# TM.net
KiCad netlist of a schematic drawn in EAGLE
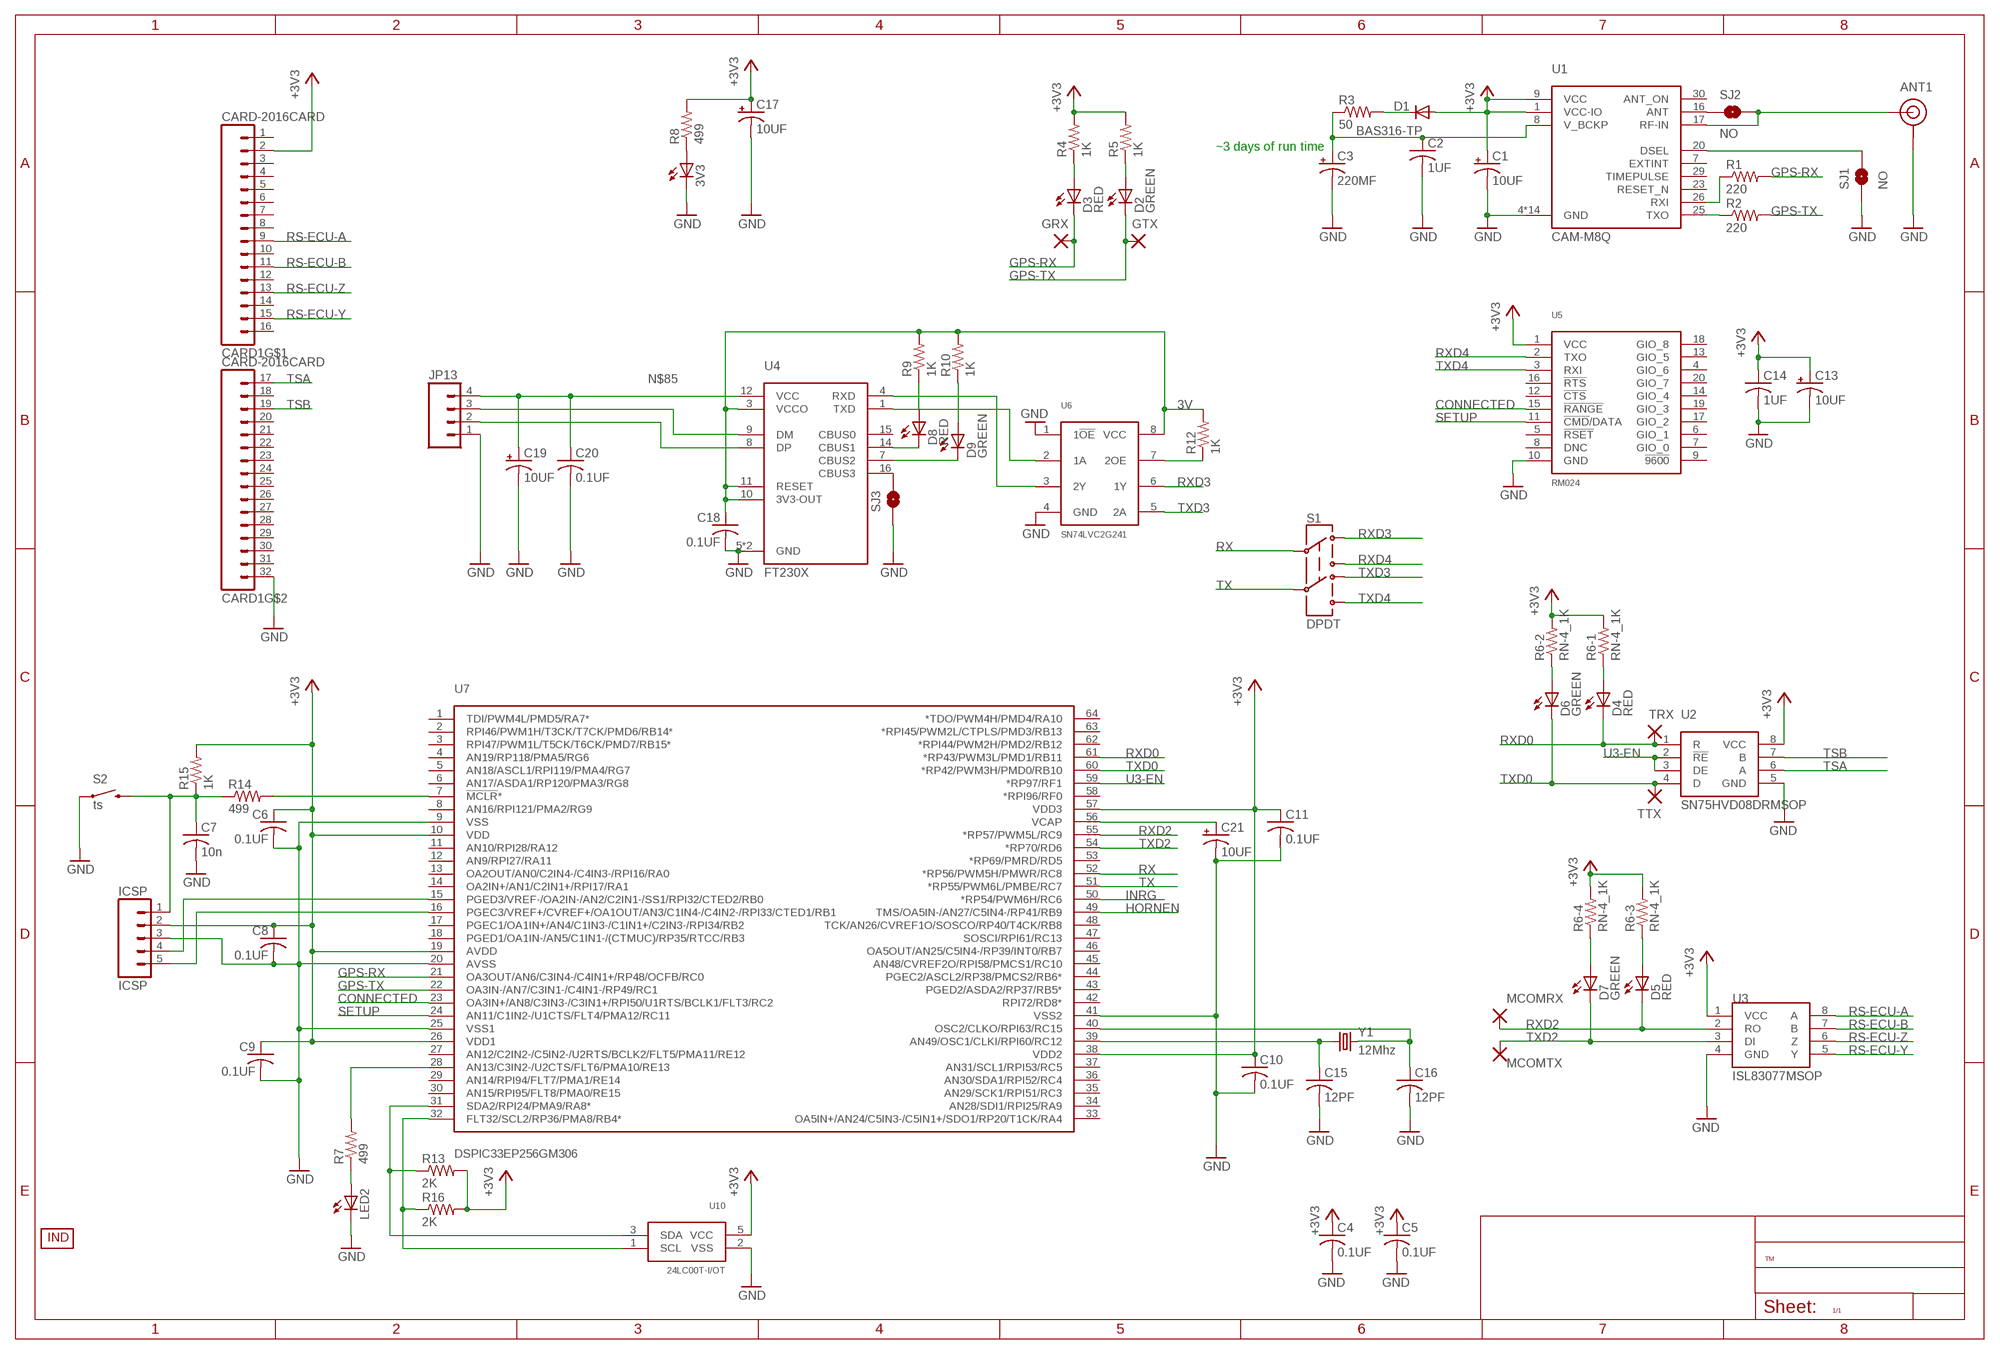
[diagram p0: schematic, sheet 1]

(export (version "E")
  (design (tool "Eeschema 10.0.6"))
  (components
    (comp (ref "3V3")
      (value "LEDCHIP-LED0805")
      (footprint "eagle-import:CHIP-LED0805")
      (libsource (lib "eagle-import") (part "LEDCHIP-LED0805"))
    )
    (comp (ref "ANT1")
      (value "CONMCX002")
      (footprint "eagle-import:CONSMA002")
      (libsource (lib "eagle-import") (part "SMA"))
    )
    (comp (ref "C1")
      (value "10UF")
      (footprint "eagle-import:EIA3216-16V")
      (fields (field (name "PARTNO") "T491A106M016AT"))
      (libsource (lib "eagle-import") (part "CAP-POL_10UF_16V"))
    )
    (comp (ref "C2")
      (value "1UF")
      (footprint "eagle-import:0805")
      (fields (field (name "PARTNO") "UMK212F105ZG-T"))
      (libsource (lib "eagle-import") (part "CAP_1UF_50V_0805"))
    )
    (comp (ref "C3")
      (value "220MF")
      (footprint "eagle-import:EEC-S0HD224V")
      (fields (field (name "PARTNO") "EEC-S0HD224V"))
      (libsource (lib "eagle-import") (part "CAP-POL_220MF_5.5V"))
    )
    (comp (ref "C4")
      (value "0.1UF")
      (footprint "eagle-import:0805")
      (fields (field (name "PARTNO") "CC0805ZRY5V9BB104"))
      (libsource (lib "eagle-import") (part "CAP_0.1UF_50V_0805"))
    )
    (comp (ref "C5")
      (value "0.1UF")
      (footprint "eagle-import:0805")
      (fields (field (name "PARTNO") "CC0805ZRY5V9BB104"))
      (libsource (lib "eagle-import") (part "CAP_0.1UF_50V_0805"))
    )
    (comp (ref "C6")
      (value "0.1UF")
      (footprint "eagle-import:0805")
      (fields (field (name "PARTNO") "CC0805ZRY5V9BB104"))
      (libsource (lib "eagle-import") (part "CAP_0.1UF_50V_0805"))
    )
    (comp (ref "C7")
      (value "10n")
      (footprint "eagle-import:C0805")
      (libsource (lib "eagle-import") (part "C-USC0805"))
    )
    (comp (ref "C8")
      (value "0.1UF")
      (footprint "eagle-import:0805")
      (fields (field (name "PARTNO") "CC0805ZRY5V9BB104"))
      (libsource (lib "eagle-import") (part "CAP_0.1UF_50V_0805"))
    )
    (comp (ref "C9")
      (value "0.1UF")
      (footprint "eagle-import:0805")
      (fields (field (name "PARTNO") "CC0805ZRY5V9BB104"))
      (libsource (lib "eagle-import") (part "CAP_0.1UF_50V_0805"))
    )
    (comp (ref "C10")
      (value "0.1UF")
      (footprint "eagle-import:0805")
      (fields (field (name "PARTNO") "CC0805ZRY5V9BB104"))
      (libsource (lib "eagle-import") (part "CAP_0.1UF_50V_0805"))
    )
    (comp (ref "C11")
      (value "0.1UF")
      (footprint "eagle-import:0805")
      (fields (field (name "PARTNO") "CC0805ZRY5V9BB104"))
      (libsource (lib "eagle-import") (part "CAP_0.1UF_50V_0805"))
    )
    (comp (ref "C13")
      (value "10UF")
      (footprint "eagle-import:EIA3216-16V")
      (fields (field (name "PARTNO") "T491A106M016AT"))
      (libsource (lib "eagle-import") (part "CAP-POL_10UF_16V"))
    )
    (comp (ref "C14")
      (value "1UF")
      (footprint "eagle-import:0805")
      (fields (field (name "PARTNO") "UMK212F105ZG-T"))
      (libsource (lib "eagle-import") (part "CAP_1UF_50V_0805"))
    )
    (comp (ref "C15")
      (value "12PF")
      (footprint "eagle-import:0805")
      (fields (field (name "PARTNO") "CL21C120JBANNNC"))
      (libsource (lib "eagle-import") (part "CAP_12PF_50V_0805"))
    )
    (comp (ref "C16")
      (value "12PF")
      (footprint "eagle-import:0805")
      (fields (field (name "PARTNO") "CL21C120JBANNNC"))
      (libsource (lib "eagle-import") (part "CAP_12PF_50V_0805"))
    )
    (comp (ref "C17")
      (value "10UF")
      (footprint "eagle-import:EIA3216-16V")
      (fields (field (name "PARTNO") "T491A106M016AT"))
      (libsource (lib "eagle-import") (part "CAP-POL_10UF_16V"))
    )
    (comp (ref "C18")
      (value "0.1UF")
      (footprint "eagle-import:0805")
      (fields (field (name "PARTNO") "CC0805ZRY5V9BB104"))
      (libsource (lib "eagle-import") (part "CAP_0.1UF_50V_0805"))
    )
    (comp (ref "C19")
      (value "10UF")
      (footprint "eagle-import:EIA3216-16V")
      (fields (field (name "PARTNO") "T491A106M016AT"))
      (libsource (lib "eagle-import") (part "CAP-POL_10UF_16V"))
    )
    (comp (ref "C20")
      (value "0.1UF")
      (footprint "eagle-import:0805")
      (fields (field (name "PARTNO") "CC0805ZRY5V9BB104"))
      (libsource (lib "eagle-import") (part "CAP_0.1UF_50V_0805"))
    )
    (comp (ref "C21")
      (value "10UF")
      (footprint "eagle-import:EIA3216-16V")
      (fields (field (name "PARTNO") "T491A106M016AT"))
      (libsource (lib "eagle-import") (part "CAP-POL_10UF_16V"))
    )
    (comp (ref "CARD1")
      (value "CARD-2016CARD")
      (footprint "eagle-import:CARD-2016")
      (libsource (lib "eagle-import") (part "CARD-2016CARD"))
    )
    (comp (ref "D1")
      (value "BAS316-TP")
      (footprint "eagle-import:SOD-323")
      (libsource (lib "eagle-import") (part "DIODESOD"))
    )
    (comp (ref "D2")
      (value "GREEN")
      (footprint "eagle-import:CHIP_LED0805")
      (fields (field (name "PARTNO") "LTST-S220GKT"))
      (libsource (lib "eagle-import") (part "LED_GREEN"))
    )
    (comp (ref "D3")
      (value "RED")
      (footprint "eagle-import:CHIP_LED0805")
      (fields (field (name "PARTNO") "LH R974-LP-1"))
      (libsource (lib "eagle-import") (part "LED_RED"))
    )
    (comp (ref "D4")
      (value "RED")
      (footprint "eagle-import:CHIP_LED0805")
      (fields (field (name "PARTNO") "LH R974-LP-1"))
      (libsource (lib "eagle-import") (part "LED_RED"))
    )
    (comp (ref "D5")
      (value "RED")
      (footprint "eagle-import:CHIP_LED0805")
      (fields (field (name "PARTNO") "LH R974-LP-1"))
      (libsource (lib "eagle-import") (part "LED_RED"))
    )
    (comp (ref "D6")
      (value "GREEN")
      (footprint "eagle-import:CHIP_LED0805")
      (fields (field (name "PARTNO") "LTST-S220GKT"))
      (libsource (lib "eagle-import") (part "LED_GREEN"))
    )
    (comp (ref "D7")
      (value "GREEN")
      (footprint "eagle-import:CHIP_LED0805")
      (fields (field (name "PARTNO") "LTST-S220GKT"))
      (libsource (lib "eagle-import") (part "LED_GREEN"))
    )
    (comp (ref "D8")
      (value "RED")
      (footprint "eagle-import:CHIP_LED0805")
      (fields (field (name "PARTNO") "LH R974-LP-1"))
      (libsource (lib "eagle-import") (part "LED_RED"))
    )
    (comp (ref "D9")
      (value "GREEN")
      (footprint "eagle-import:CHIP_LED0805")
      (fields (field (name "PARTNO") "LTST-S220GKT"))
      (libsource (lib "eagle-import") (part "LED_GREEN"))
    )
    (comp (ref "GRX")
      (value "TP")
      (footprint "eagle-import:0603")
      (fields (field (name "PARTNO") "1625854-3"))
      (libsource (lib "eagle-import") (part "TP"))
    )
    (comp (ref "GTX")
      (value "TP")
      (footprint "eagle-import:0603")
      (fields (field (name "PARTNO") "1625854-3"))
      (libsource (lib "eagle-import") (part "TP"))
    )
    (comp (ref "ICSP")
      (value "ICSP")
      (footprint "eagle-import:1X05_LOCK_LONGPADS")
      (libsource (lib "eagle-import") (part "M05LOCK_LONGPADS"))
    )
    (comp (ref "JP13")
      (value "M04POLAR_LOCK")
      (footprint "eagle-import:MOLEX-1X4_LOCK")
      (libsource (lib "eagle-import") (part "M04POLAR_LOCK"))
    )
    (comp (ref "LED2")
      (value "LEDCHIP-LED0805")
      (footprint "eagle-import:CHIP-LED0805")
      (libsource (lib "eagle-import") (part "LEDCHIP-LED0805"))
    )
    (comp (ref "MCOMRX")
      (value "TP")
      (footprint "eagle-import:0603")
      (fields (field (name "PARTNO") "1625854-3"))
      (libsource (lib "eagle-import") (part "TP"))
    )
    (comp (ref "MCOMTX")
      (value "TP")
      (footprint "eagle-import:0603")
      (fields (field (name "PARTNO") "1625854-3"))
      (libsource (lib "eagle-import") (part "TP"))
    )
    (comp (ref "R1")
      (value "220")
      (footprint "eagle-import:0805")
      (fields (field (name "PARTNO") "RC0805FR-07220RL"))
      (libsource (lib "eagle-import") (part "RES_220_1%_0805"))
    )
    (comp (ref "R2")
      (value "220")
      (footprint "eagle-import:0805")
      (fields (field (name "PARTNO") "RC0805FR-07220RL"))
      (libsource (lib "eagle-import") (part "RES_220_1%_0805"))
    )
    (comp (ref "R3")
      (value "50")
      (footprint "eagle-import:R2010")
      (libsource (lib "eagle-import") (part "RESISTOR2010"))
    )
    (comp (ref "R4")
      (value "1K")
      (footprint "eagle-import:0805")
      (fields (field (name "PARTNO") "RC0805FR-071KL"))
      (libsource (lib "eagle-import") (part "RES_1K_1%_0805"))
    )
    (comp (ref "R5")
      (value "1K")
      (footprint "eagle-import:0805")
      (fields (field (name "PARTNO") "RC0805FR-071KL"))
      (libsource (lib "eagle-import") (part "RES_1K_1%_0805"))
    )
    (comp (ref "R6")
      (value "RN-4_1K")
      (footprint "eagle-import:MNR14")
      (fields (field (name "PARTNO") "MNR14ERAPJ102"))
      (libsource (lib "eagle-import") (part "RN-4_1K"))
    )
    (comp (ref "R7")
      (value "499")
      (footprint "eagle-import:0805")
      (fields (field (name "PARTNO") "RC0805FR-07499RL"))
      (libsource (lib "eagle-import") (part "RES_499_1%_0805"))
    )
    (comp (ref "R8")
      (value "499")
      (footprint "eagle-import:0805")
      (fields (field (name "PARTNO") "RC0805FR-07499RL"))
      (libsource (lib "eagle-import") (part "RES_499_1%_0805"))
    )
    (comp (ref "R9")
      (value "1K")
      (footprint "eagle-import:0805")
      (fields (field (name "PARTNO") "RC0805FR-071KL"))
      (libsource (lib "eagle-import") (part "RES_1K_1%_0805"))
    )
    (comp (ref "R10")
      (value "1K")
      (footprint "eagle-import:0805")
      (fields (field (name "PARTNO") "RC0805FR-071KL"))
      (libsource (lib "eagle-import") (part "RES_1K_1%_0805"))
    )
    (comp (ref "R12")
      (value "1K")
      (footprint "eagle-import:0805")
      (fields (field (name "PARTNO") "RC0805FR-071KL"))
      (libsource (lib "eagle-import") (part "RES_1K_1%_0805"))
    )
    (comp (ref "R13")
      (value "2K")
      (footprint "eagle-import:0805")
      (fields (field (name "PARTNO") "RC0805FR-072KL"))
      (libsource (lib "eagle-import") (part "RES_2K_1%_0805"))
    )
    (comp (ref "R14")
      (value "499")
      (footprint "eagle-import:0805")
      (fields (field (name "PARTNO") "RC0805FR-07499RL"))
      (libsource (lib "eagle-import") (part "RES_499_1%_0805"))
    )
    (comp (ref "R15")
      (value "1K")
      (footprint "eagle-import:0805")
      (fields (field (name "PARTNO") "RC0805FR-071KL"))
      (libsource (lib "eagle-import") (part "RES_1K_1%_0805"))
    )
    (comp (ref "R16")
      (value "2K")
      (footprint "eagle-import:0805")
      (fields (field (name "PARTNO") "RC0805FR-072KL"))
      (libsource (lib "eagle-import") (part "RES_2K_1%_0805"))
    )
    (comp (ref "S1")
      (value "DPDT")
      (footprint "eagle-import:AYZ0202")
      (libsource (lib "eagle-import") (part "SWITCH-DPDTAYZ0202"))
    )
    (comp (ref "S2")
      (value "ts")
      (footprint "eagle-import:TACTILE_SWITCH_SMD-2")
      (libsource (lib "eagle-import") (part "SWITCH-MOMENTARY-2SMD-2"))
    )
    (comp (ref "SJ1")
      (value "NO")
      (footprint "eagle-import:SJ_2S-NO")
      (libsource (lib "eagle-import") (part "SOLDERJUMPERNO"))
    )
    (comp (ref "SJ2")
      (value "NO")
      (footprint "eagle-import:SJ_2S-NO")
      (libsource (lib "eagle-import") (part "SOLDERJUMPERNO"))
    )
    (comp (ref "SJ3")
      (value "JUMPER-PAD-2-NOYES_SILK")
      (footprint "eagle-import:PAD-JUMPER-2-NO_YES_SILK")
      (libsource (lib "eagle-import") (part "JUMPER-PAD-2-NOYES_SILK"))
    )
    (comp (ref "TRX")
      (value "TP")
      (footprint "eagle-import:0603")
      (fields (field (name "PARTNO") "1625854-3"))
      (libsource (lib "eagle-import") (part "TP"))
    )
    (comp (ref "TTX")
      (value "TP")
      (footprint "eagle-import:0603")
      (fields (field (name "PARTNO") "1625854-3"))
      (libsource (lib "eagle-import") (part "TP"))
    )
    (comp (ref "U$3")
      (value "INDPK1")
      (footprint "eagle-import:PICKIT-PIN-1")
      (libsource (lib "eagle-import") (part "INDPK1"))
    )
    (comp (ref "U1")
      (value "CAM-M8Q")
      (footprint "eagle-import:CAM-M8Q")
      (libsource (lib "eagle-import") (part "CAM-M8Q"))
    )
    (comp (ref "U2")
      (value "SN75HVD08DRMSOP")
      (footprint "eagle-import:MSOP-8")
      (fields (field (name "PARTNO") "ISL83072EIUZA-T"))
      (libsource (lib "eagle-import") (part "SN75HVD08DRMSOP"))
    )
    (comp (ref "U3")
      (value "ISL83077MSOP")
      (footprint "eagle-import:MSOP8")
      (fields (field (name "PARTNO") "ISL83072EIUZA-T"))
      (libsource (lib "eagle-import") (part "ISL83077MSOP"))
    )
    (comp (ref "U4")
      (value "FT230X")
      (footprint "eagle-import:SSOP-16")
      (fields (field (name "PARTNO") "FT230XS-R"))
      (libsource (lib "eagle-import") (part "FT230X"))
    )
    (comp (ref "U5")
      (value "RM024")
      (footprint "eagle-import:RM024-TH")
      (libsource (lib "eagle-import") (part "RM024"))
    )
    (comp (ref "U6")
      (value "SN74LVC2G241")
      (footprint "eagle-import:VFSOP-8")
      (fields (field (name "PARTNO") "SN74LVC2G241DCUR"))
      (libsource (lib "eagle-import") (part "SN74LVC2G241"))
    )
    (comp (ref "U7")
      (value "DSPIC33EP256GM306")
      (footprint "eagle-import:TQFP-64")
      (libsource (lib "eagle-import") (part "DSPIC33EP256GM306"))
    )
    (comp (ref "U10")
      (value "24LC00T-I/OT")
      (footprint "eagle-import:SOT23-5")
      (libsource (lib "eagle-import") (part "24LC00T-I/OT"))
    )
    (comp (ref "Y1")
      (value "12Mhz")
      (footprint "eagle-import:CRYSTAL-SMD-5X3")
      (libsource (lib "eagle-import") (part "CRYSTAL5X3"))
    )
  )
  (nets
    (net (code "1") (name "+3V3") (class "Default")
      (node (ref "C1") (pin "A") (pinfunction "+_A") (pintype "passive"))
      (node (ref "C10") (pin "1") (pinfunction "+_1") (pintype "passive"))
      (node (ref "C11") (pin "1") (pinfunction "+_1") (pintype "passive"))
      (node (ref "C13") (pin "A") (pinfunction "+_A") (pintype "passive"))
      (node (ref "C14") (pin "1") (pinfunction "+_1") (pintype "passive"))
      (node (ref "C17") (pin "A") (pinfunction "+_A") (pintype "passive"))
      (node (ref "C4") (pin "1") (pinfunction "+_1") (pintype "passive"))
      (node (ref "C5") (pin "1") (pinfunction "+_1") (pintype "passive"))
      (node (ref "C6") (pin "1") (pinfunction "+_1") (pintype "passive"))
      (node (ref "C8") (pin "1") (pinfunction "+_1") (pintype "passive"))
      (node (ref "C9") (pin "1") (pinfunction "+_1") (pintype "passive"))
      (node (ref "CARD1") (pin "2") (pinfunction "2_2") (pintype "passive"))
      (node (ref "D1") (pin "2") (pinfunction "A_2") (pintype "passive"))
      (node (ref "ICSP") (pin "2") (pinfunction "2_2") (pintype "passive"))
      (node (ref "R13") (pin "2") (pinfunction "2_2") (pintype "passive"))
      (node (ref "R15") (pin "2") (pinfunction "2_2") (pintype "passive"))
      (node (ref "R16") (pin "2") (pinfunction "2_2") (pintype "passive"))
      (node (ref "R4") (pin "2") (pinfunction "2_2") (pintype "passive"))
      (node (ref "R5") (pin "2") (pinfunction "2_2") (pintype "passive"))
      (node (ref "R6") (pin "5") (pinfunction "2_5") (pintype "passive"))
      (node (ref "R6") (pin "6") (pinfunction "2_6") (pintype "passive"))
      (node (ref "R6") (pin "7") (pinfunction "2_7") (pintype "passive"))
      (node (ref "R6") (pin "8") (pinfunction "2_8") (pintype "passive"))
      (node (ref "R8") (pin "2") (pinfunction "2_2") (pintype "passive"))
      (node (ref "U1") (pin "1") (pinfunction "VCC-IO_1") (pintype "bidirectional"))
      (node (ref "U1") (pin "9") (pinfunction "VCC_9") (pintype "bidirectional"))
      (node (ref "U10") (pin "5") (pinfunction "VCC_5") (pintype "bidirectional"))
      (node (ref "U2") (pin "8") (pinfunction "VCC_8") (pintype "bidirectional"))
      (node (ref "U3") (pin "1") (pinfunction "VCC_1") (pintype "bidirectional"))
      (node (ref "U5") (pin "1") (pinfunction "VCC_1") (pintype "bidirectional"))
      (node (ref "U7") (pin "10") (pinfunction "VDD_10") (pintype "bidirectional"))
      (node (ref "U7") (pin "19") (pinfunction "AVDD_19") (pintype "bidirectional"))
      (node (ref "U7") (pin "26") (pinfunction "VDD1_26") (pintype "bidirectional"))
      (node (ref "U7") (pin "38") (pinfunction "VDD2_38") (pintype "bidirectional"))
      (node (ref "U7") (pin "57") (pinfunction "VDD3_57") (pintype "bidirectional"))
    )
    (net (code "2") (name "/3V") (class "Default")
      (node (ref "C18") (pin "1") (pinfunction "+_1") (pintype "passive"))
      (node (ref "R10") (pin "2") (pinfunction "2_2") (pintype "passive"))
      (node (ref "R12") (pin "2") (pinfunction "2_2") (pintype "passive"))
      (node (ref "R9") (pin "2") (pinfunction "2_2") (pintype "passive"))
      (node (ref "U4") (pin "10") (pinfunction "3V3-OUT_10") (pintype "bidirectional"))
      (node (ref "U4") (pin "11") (pinfunction "RESET_11") (pintype "bidirectional"))
      (node (ref "U4") (pin "3") (pinfunction "VCCO_3") (pintype "bidirectional"))
      (node (ref "U6") (pin "8") (pinfunction "VCC_8") (pintype "bidirectional"))
    )
    (net (code "3") (name "/CONNECTED") (class "Default")
      (node (ref "U5") (pin "15") (pinfunction "~{RANGE}_15") (pintype "bidirectional"))
      (node (ref "U7") (pin "23") (pinfunction "OA3IN+/AN8/C3IN3-/C3IN1+/RPI50/U1RTS/BCLK1/FLT3/RC2_23") (pintype "bidirectional"))
    )
    (net (code "4") (name "/GPS-RX") (class "Default")
      (node (ref "D3") (pin "C") (pinfunction "C_C") (pintype "passive"))
      (node (ref "GRX") (pin "1") (pinfunction "P$1_1") (pintype "bidirectional"))
      (node (ref "GRX") (pin "2") (pinfunction "P$1_2") (pintype "bidirectional"))
      (node (ref "R1") (pin "2") (pinfunction "2_2") (pintype "passive"))
      (node (ref "U7") (pin "21") (pinfunction "OA3OUT/AN6/C3IN4-/C4IN1+/RP48/OCFB/RC0_21") (pintype "bidirectional"))
    )
    (net (code "5") (name "/GPS-TX") (class "Default")
      (node (ref "D2") (pin "C") (pinfunction "C_C") (pintype "passive"))
      (node (ref "GTX") (pin "1") (pinfunction "P$1_1") (pintype "bidirectional"))
      (node (ref "GTX") (pin "2") (pinfunction "P$1_2") (pintype "bidirectional"))
      (node (ref "R2") (pin "2") (pinfunction "2_2") (pintype "passive"))
      (node (ref "U7") (pin "22") (pinfunction "OA3IN-/AN7/C3IN1-/C4IN1-/RP49/RC1_22") (pintype "bidirectional"))
    )
    (net (code "6") (name "/HORNEN") (class "Default")
      (node (ref "U7") (pin "49") (pinfunction "TMS/OA5IN-/AN27/C5IN4-/RP41/RB9_49") (pintype "bidirectional"))
    )
    (net (code "7") (name "/INRG") (class "Default")
      (node (ref "U7") (pin "50") (pinfunction "*RP54/PWM6H/RC6_50") (pintype "bidirectional"))
    )
    (net (code "8") (name "/N$85") (class "Default")
      (node (ref "C19") (pin "A") (pinfunction "+_A") (pintype "passive"))
      (node (ref "C20") (pin "1") (pinfunction "+_1") (pintype "passive"))
      (node (ref "JP13") (pin "4") (pinfunction "4_4") (pintype "passive"))
      (node (ref "U4") (pin "12") (pinfunction "VCC_12") (pintype "bidirectional"))
    )
    (net (code "9") (name "/RS-ECU-A") (class "Default")
      (node (ref "CARD1") (pin "9") (pinfunction "9_9") (pintype "passive"))
      (node (ref "U3") (pin "8") (pinfunction "A_8") (pintype "bidirectional"))
    )
    (net (code "10") (name "/RS-ECU-B") (class "Default")
      (node (ref "CARD1") (pin "11") (pinfunction "11_11") (pintype "passive"))
      (node (ref "U3") (pin "7") (pinfunction "B_7") (pintype "bidirectional"))
    )
    (net (code "11") (name "/RS-ECU-Y") (class "Default")
      (node (ref "CARD1") (pin "15") (pinfunction "15_15") (pintype "passive"))
      (node (ref "U3") (pin "5") (pinfunction "Y_5") (pintype "bidirectional"))
    )
    (net (code "12") (name "/RS-ECU-Z") (class "Default")
      (node (ref "CARD1") (pin "13") (pinfunction "13_13") (pintype "passive"))
      (node (ref "U3") (pin "6") (pinfunction "Z_6") (pintype "bidirectional"))
    )
    (net (code "13") (name "/RX") (class "Default")
      (node (ref "S1") (pin "2") (pinfunction "2_2") (pintype "bidirectional"))
      (node (ref "U7") (pin "52") (pinfunction "*RP56/PWM5H/PMWR/RC8_52") (pintype "bidirectional"))
    )
    (net (code "14") (name "/RXD0") (class "Default")
      (node (ref "D4") (pin "C") (pinfunction "C_C") (pintype "passive"))
      (node (ref "TRX") (pin "1") (pinfunction "P$1_1") (pintype "bidirectional"))
      (node (ref "TRX") (pin "2") (pinfunction "P$1_2") (pintype "bidirectional"))
      (node (ref "U2") (pin "1") (pinfunction "R_1") (pintype "bidirectional"))
      (node (ref "U7") (pin "61") (pinfunction "*RP43/PWM3L/PMD1/RB11_61") (pintype "bidirectional"))
    )
    (net (code "15") (name "/RXD2") (class "Default")
      (node (ref "D5") (pin "C") (pinfunction "C_C") (pintype "passive"))
      (node (ref "MCOMRX") (pin "1") (pinfunction "P$1_1") (pintype "bidirectional"))
      (node (ref "MCOMRX") (pin "2") (pinfunction "P$1_2") (pintype "bidirectional"))
      (node (ref "U3") (pin "2") (pinfunction "RO_2") (pintype "bidirectional"))
      (node (ref "U7") (pin "55") (pinfunction "*RP57/PWM5L/RC9_55") (pintype "bidirectional"))
    )
    (net (code "16") (name "/RXD3") (class "Default")
      (node (ref "S1") (pin "1") (pinfunction "1_1") (pintype "bidirectional"))
      (node (ref "U6") (pin "6") (pinfunction "1Y_6") (pintype "bidirectional"))
    )
    (net (code "17") (name "/RXD4") (class "Default")
      (node (ref "S1") (pin "3") (pinfunction "3_3") (pintype "bidirectional"))
      (node (ref "U5") (pin "2") (pinfunction "TXO_2") (pintype "bidirectional"))
    )
    (net (code "18") (name "/SETUP") (class "Default")
      (node (ref "U5") (pin "11") (pinfunction "~{CMD}/DATA_11") (pintype "bidirectional"))
      (node (ref "U7") (pin "24") (pinfunction "AN11/C1IN2-/U1CTS/FLT4/PMA12/RC11_24") (pintype "bidirectional"))
    )
    (net (code "19") (name "/TSA") (class "Default")
      (node (ref "CARD1") (pin "17") (pinfunction "1_17") (pintype "passive"))
      (node (ref "U2") (pin "6") (pinfunction "A_6") (pintype "bidirectional"))
    )
    (net (code "20") (name "/TSB") (class "Default")
      (node (ref "CARD1") (pin "19") (pinfunction "3_19") (pintype "passive"))
      (node (ref "U2") (pin "7") (pinfunction "B_7") (pintype "bidirectional"))
    )
    (net (code "21") (name "/TX") (class "Default")
      (node (ref "S1") (pin "5") (pinfunction "5_5") (pintype "bidirectional"))
      (node (ref "U7") (pin "51") (pinfunction "*RP55/PWM6L/PMBE/RC7_51") (pintype "bidirectional"))
    )
    (net (code "22") (name "/TXD0") (class "Default")
      (node (ref "D6") (pin "C") (pinfunction "C_C") (pintype "passive"))
      (node (ref "TTX") (pin "1") (pinfunction "P$1_1") (pintype "bidirectional"))
      (node (ref "TTX") (pin "2") (pinfunction "P$1_2") (pintype "bidirectional"))
      (node (ref "U2") (pin "4") (pinfunction "D_4") (pintype "bidirectional"))
      (node (ref "U7") (pin "60") (pinfunction "*RP42/PWM3H/PMD0/RB10_60") (pintype "bidirectional"))
    )
    (net (code "23") (name "/TXD2") (class "Default")
      (node (ref "D7") (pin "C") (pinfunction "C_C") (pintype "passive"))
      (node (ref "MCOMTX") (pin "1") (pinfunction "P$1_1") (pintype "bidirectional"))
      (node (ref "MCOMTX") (pin "2") (pinfunction "P$1_2") (pintype "bidirectional"))
      (node (ref "U3") (pin "3") (pinfunction "DI_3") (pintype "bidirectional"))
      (node (ref "U7") (pin "54") (pinfunction "*RP70/RD6_54") (pintype "bidirectional"))
    )
    (net (code "24") (name "/TXD3") (class "Default")
      (node (ref "S1") (pin "4") (pinfunction "4_4") (pintype "bidirectional"))
      (node (ref "U6") (pin "5") (pinfunction "2A_5") (pintype "bidirectional"))
    )
    (net (code "25") (name "/TXD4") (class "Default")
      (node (ref "S1") (pin "6") (pinfunction "6_6") (pintype "bidirectional"))
      (node (ref "U5") (pin "3") (pinfunction "RXI_3") (pintype "bidirectional"))
    )
    (net (code "26") (name "/U3-EN") (class "Default")
      (node (ref "U2") (pin "2") (pinfunction "~{RE}_2") (pintype "bidirectional"))
      (node (ref "U2") (pin "3") (pinfunction "DE_3") (pintype "bidirectional"))
      (node (ref "U7") (pin "59") (pinfunction "*RP97/RF1_59") (pintype "bidirectional"))
    )
    (net (code "27") (name "GND") (class "Default")
      (node (ref "3V3") (pin "C") (pinfunction "C_C") (pintype "passive"))
      (node (ref "ANT1") (pin "1") (pinfunction "GND_1") (pintype "bidirectional"))
      (node (ref "ANT1") (pin "2") (pinfunction "GND_2") (pintype "bidirectional"))
      (node (ref "ANT1") (pin "3") (pinfunction "GND_3") (pintype "bidirectional"))
      (node (ref "ANT1") (pin "4") (pinfunction "GND_4") (pintype "bidirectional"))
      (node (ref "C1") (pin "C") (pinfunction "-_C") (pintype "passive"))
      (node (ref "C10") (pin "2") (pinfunction "-_2") (pintype "passive"))
      (node (ref "C11") (pin "2") (pinfunction "-_2") (pintype "passive"))
      (node (ref "C13") (pin "C") (pinfunction "-_C") (pintype "passive"))
      (node (ref "C14") (pin "2") (pinfunction "-_2") (pintype "passive"))
      (node (ref "C15") (pin "2") (pinfunction "-_2") (pintype "passive"))
      (node (ref "C16") (pin "2") (pinfunction "-_2") (pintype "passive"))
      (node (ref "C17") (pin "C") (pinfunction "-_C") (pintype "passive"))
      (node (ref "C18") (pin "2") (pinfunction "-_2") (pintype "passive"))
      (node (ref "C19") (pin "C") (pinfunction "-_C") (pintype "passive"))
      (node (ref "C2") (pin "2") (pinfunction "-_2") (pintype "passive"))
      (node (ref "C20") (pin "2") (pinfunction "-_2") (pintype "passive"))
      (node (ref "C21") (pin "C") (pinfunction "-_C") (pintype "passive"))
      (node (ref "C3") (pin "-") (pinfunction "-_-") (pintype "passive"))
      (node (ref "C4") (pin "2") (pinfunction "-_2") (pintype "passive"))
      (node (ref "C5") (pin "2") (pinfunction "-_2") (pintype "passive"))
      (node (ref "C6") (pin "2") (pinfunction "-_2") (pintype "passive"))
      (node (ref "C7") (pin "2") (pinfunction "2_2") (pintype "passive"))
      (node (ref "C8") (pin "2") (pinfunction "-_2") (pintype "passive"))
      (node (ref "C9") (pin "2") (pinfunction "-_2") (pintype "passive"))
      (node (ref "CARD1") (pin "32") (pinfunction "16_32") (pintype "passive"))
      (node (ref "ICSP") (pin "3") (pinfunction "3_3") (pintype "passive"))
      (node (ref "JP13") (pin "1") (pinfunction "1_1") (pintype "passive"))
      (node (ref "LED2") (pin "C") (pinfunction "C_C") (pintype "passive"))
      (node (ref "S2") (pin "2") (pinfunction "1_2") (pintype "passive"))
      (node (ref "SJ1") (pin "1") (pinfunction "1_1") (pintype "passive"))
      (node (ref "SJ3") (pin "1") (pinfunction "1_1") (pintype "passive"))
      (node (ref "U1") (pin "10") (pinfunction "GND_10") (pintype "bidirectional"))
      (node (ref "U1") (pin "11") (pinfunction "GND_11") (pintype "bidirectional"))
      (node (ref "U1") (pin "12") (pinfunction "GND_12") (pintype "bidirectional"))
      (node (ref "U1") (pin "13") (pinfunction "GND_13") (pintype "bidirectional"))
      (node (ref "U1") (pin "14") (pinfunction "GND_14") (pintype "bidirectional"))
      (node (ref "U1") (pin "15") (pinfunction "GND_15") (pintype "bidirectional"))
      (node (ref "U1") (pin "18") (pinfunction "GND_18") (pintype "bidirectional"))
      (node (ref "U1") (pin "19") (pinfunction "GND_19") (pintype "bidirectional"))
      (node (ref "U1") (pin "21") (pinfunction "GND_21") (pintype "bidirectional"))
      (node (ref "U1") (pin "22") (pinfunction "GND_22") (pintype "bidirectional"))
      (node (ref "U1") (pin "27") (pinfunction "GND_27") (pintype "bidirectional"))
      (node (ref "U1") (pin "31") (pinfunction "GND_31") (pintype "bidirectional"))
      (node (ref "U1") (pin "4") (pinfunction "GND_4") (pintype "bidirectional"))
      (node (ref "U1") (pin "5") (pinfunction "GND_5") (pintype "bidirectional"))
      (node (ref "U10") (pin "2") (pinfunction "VSS_2") (pintype "bidirectional"))
      (node (ref "U2") (pin "5") (pinfunction "GND_5") (pintype "bidirectional"))
      (node (ref "U3") (pin "4") (pinfunction "GND_4") (pintype "bidirectional"))
      (node (ref "U4") (pin "13") (pinfunction "GND_13") (pintype "bidirectional"))
      (node (ref "U4") (pin "5") (pinfunction "GND_5") (pintype "bidirectional"))
      (node (ref "U5") (pin "10") (pinfunction "GND_10") (pintype "bidirectional"))
      (node (ref "U6") (pin "1") (pinfunction "1~{OE}_1") (pintype "bidirectional"))
      (node (ref "U6") (pin "4") (pinfunction "GND_4") (pintype "bidirectional"))
      (node (ref "U7") (pin "20") (pinfunction "AVSS_20") (pintype "bidirectional"))
      (node (ref "U7") (pin "25") (pinfunction "VSS1_25") (pintype "bidirectional"))
      (node (ref "U7") (pin "41") (pinfunction "VSS2_41") (pintype "bidirectional"))
      (node (ref "U7") (pin "9") (pinfunction "VSS_9") (pintype "bidirectional"))
    )
    (net (code "28") (name "Net-(3V3-PadA)") (class "Default")
      (node (ref "3V3") (pin "A") (pinfunction "A_A") (pintype "passive"))
      (node (ref "R8") (pin "1") (pinfunction "1_1") (pintype "passive"))
    )
    (net (code "29") (name "Net-(ANT1-SIGNAL)") (class "Default")
      (node (ref "ANT1") (pin "C") (pinfunction "SIGNAL_C") (pintype "bidirectional"))
      (node (ref "SJ2") (pin "2") (pinfunction "2_2") (pintype "passive"))
      (node (ref "U1") (pin "17") (pinfunction "RF-IN_17") (pintype "bidirectional"))
    )
    (net (code "30") (name "Net-(C2-+)") (class "Default")
      (node (ref "C2") (pin "1") (pinfunction "+_1") (pintype "passive"))
      (node (ref "C3") (pin "+") (pinfunction "+_+") (pintype "passive"))
      (node (ref "R3") (pin "1") (pinfunction "1_1") (pintype "passive"))
      (node (ref "U1") (pin "8") (pinfunction "V_BCKP_8") (pintype "bidirectional"))
    )
    (net (code "31") (name "Net-(C15-+)") (class "Default")
      (node (ref "C15") (pin "1") (pinfunction "+_1") (pintype "passive"))
      (node (ref "U7") (pin "39") (pinfunction "AN49/OSC1/CLKI/RPI60/RC12_39") (pintype "bidirectional"))
      (node (ref "Y1") (pin "1") (pinfunction "1_1") (pintype "passive"))
    )
    (net (code "32") (name "Net-(C16-+)") (class "Default")
      (node (ref "C16") (pin "1") (pinfunction "+_1") (pintype "passive"))
      (node (ref "U7") (pin "40") (pinfunction "OSC2/CLKO/RPI63/RC15_40") (pintype "bidirectional"))
      (node (ref "Y1") (pin "3") (pinfunction "2_3") (pintype "passive"))
    )
    (net (code "33") (name "Net-(C21-+)") (class "Default")
      (node (ref "C21") (pin "A") (pinfunction "+_A") (pintype "passive"))
      (node (ref "U7") (pin "56") (pinfunction "VCAP_56") (pintype "bidirectional"))
    )
    (net (code "34") (name "Net-(D1-C)") (class "Default")
      (node (ref "D1") (pin "1") (pinfunction "C_1") (pintype "passive"))
      (node (ref "R3") (pin "2") (pinfunction "2_2") (pintype "passive"))
    )
    (net (code "35") (name "Net-(D2-PadA)") (class "Default")
      (node (ref "D2") (pin "A") (pinfunction "A_A") (pintype "passive"))
      (node (ref "R5") (pin "1") (pinfunction "1_1") (pintype "passive"))
    )
    (net (code "36") (name "Net-(D3-PadA)") (class "Default")
      (node (ref "D3") (pin "A") (pinfunction "A_A") (pintype "passive"))
      (node (ref "R4") (pin "1") (pinfunction "1_1") (pintype "passive"))
    )
    (net (code "37") (name "Net-(D4-PadA)") (class "Default")
      (node (ref "D4") (pin "A") (pinfunction "A_A") (pintype "passive"))
      (node (ref "R6") (pin "1") (pinfunction "1_1") (pintype "passive"))
    )
    (net (code "38") (name "Net-(D8-PadA)") (class "Default")
      (node (ref "D8") (pin "A") (pinfunction "A_A") (pintype "passive"))
      (node (ref "R9") (pin "1") (pinfunction "1_1") (pintype "passive"))
    )
    (net (code "39") (name "Net-(D9-PadA)") (class "Default")
      (node (ref "D9") (pin "A") (pinfunction "A_A") (pintype "passive"))
      (node (ref "R10") (pin "1") (pinfunction "1_1") (pintype "passive"))
    )
    (net (code "40") (name "Net-(LED2-PadA)") (class "Default")
      (node (ref "LED2") (pin "A") (pinfunction "A_A") (pintype "passive"))
      (node (ref "R7") (pin "1") (pinfunction "1_1") (pintype "passive"))
    )
    (net (code "41") (name "Net-(R6B-1)") (class "Default")
      (node (ref "D6") (pin "A") (pinfunction "A_A") (pintype "passive"))
      (node (ref "R6") (pin "2") (pinfunction "1_2") (pintype "passive"))
    )
    (net (code "42") (name "Net-(R6C-1)") (class "Default")
      (node (ref "D5") (pin "A") (pinfunction "A_A") (pintype "passive"))
      (node (ref "R6") (pin "3") (pinfunction "1_3") (pintype "passive"))
    )
    (net (code "43") (name "Net-(R6D-1)") (class "Default")
      (node (ref "D7") (pin "A") (pinfunction "A_A") (pintype "passive"))
      (node (ref "R6") (pin "4") (pinfunction "1_4") (pintype "passive"))
    )
    (net (code "44") (name "Net-(S2-2)") (class "Default")
      (node (ref "C7") (pin "1") (pinfunction "1_1") (pintype "passive"))
      (node (ref "ICSP") (pin "1") (pinfunction "1_1") (pintype "passive"))
      (node (ref "R14") (pin "1") (pinfunction "1_1") (pintype "passive"))
      (node (ref "R15") (pin "1") (pinfunction "1_1") (pintype "passive"))
      (node (ref "S2") (pin "1") (pinfunction "2_1") (pintype "passive"))
    )
    (net (code "45") (name "Net-(U1-ANT)") (class "Default")
      (node (ref "SJ2") (pin "1") (pinfunction "1_1") (pintype "passive"))
      (node (ref "U1") (pin "16") (pinfunction "ANT_16") (pintype "bidirectional"))
    )
    (net (code "46") (name "Net-(U1-DSEL)") (class "Default")
      (node (ref "SJ1") (pin "2") (pinfunction "2_2") (pintype "passive"))
      (node (ref "U1") (pin "20") (pinfunction "DSEL_20") (pintype "bidirectional"))
    )
    (net (code "47") (name "Net-(U1-RXI)") (class "Default")
      (node (ref "R1") (pin "1") (pinfunction "1_1") (pintype "passive"))
      (node (ref "U1") (pin "26") (pinfunction "RXI_26") (pintype "bidirectional"))
    )
    (net (code "48") (name "Net-(U1-TXO)") (class "Default")
      (node (ref "R2") (pin "1") (pinfunction "1_1") (pintype "passive"))
      (node (ref "U1") (pin "25") (pinfunction "TXO_25") (pintype "bidirectional"))
    )
    (net (code "49") (name "Net-(U4-CBUS1)") (class "Default")
      (node (ref "D8") (pin "C") (pinfunction "C_C") (pintype "passive"))
      (node (ref "U4") (pin "14") (pinfunction "CBUS1_14") (pintype "bidirectional"))
    )
    (net (code "50") (name "Net-(U4-CBUS2)") (class "Default")
      (node (ref "D9") (pin "C") (pinfunction "C_C") (pintype "passive"))
      (node (ref "U4") (pin "7") (pinfunction "CBUS2_7") (pintype "bidirectional"))
    )
    (net (code "51") (name "Net-(U4-CBUS3)") (class "Default")
      (node (ref "SJ3") (pin "2") (pinfunction "2_2") (pintype "passive"))
      (node (ref "U4") (pin "16") (pinfunction "CBUS3_16") (pintype "bidirectional"))
    )
    (net (code "52") (name "Net-(U4-DM)") (class "Default")
      (node (ref "JP13") (pin "3") (pinfunction "3_3") (pintype "passive"))
      (node (ref "U4") (pin "9") (pinfunction "DM_9") (pintype "bidirectional"))
    )
    (net (code "53") (name "Net-(U4-DP)") (class "Default")
      (node (ref "JP13") (pin "2") (pinfunction "2_2") (pintype "passive"))
      (node (ref "U4") (pin "8") (pinfunction "DP_8") (pintype "bidirectional"))
    )
    (net (code "54") (name "Net-(U4-RXD)") (class "Default")
      (node (ref "U4") (pin "4") (pinfunction "RXD_4") (pintype "bidirectional"))
      (node (ref "U6") (pin "3") (pinfunction "2Y_3") (pintype "bidirectional"))
    )
    (net (code "55") (name "Net-(U4-TXD)") (class "Default")
      (node (ref "U4") (pin "1") (pinfunction "TXD_1") (pintype "bidirectional"))
      (node (ref "U6") (pin "2") (pinfunction "1A_2") (pintype "bidirectional"))
    )
    (net (code "56") (name "Net-(U6-2OE)") (class "Default")
      (node (ref "R12") (pin "1") (pinfunction "1_1") (pintype "passive"))
      (node (ref "U6") (pin "7") (pinfunction "2OE_7") (pintype "bidirectional"))
    )
    (net (code "57") (name "Net-(U7-AN13{slash}C3IN2-{slash}U2CTS{slash}FLT6{slash}PMA10{slash}RE13)") (class "Default")
      (node (ref "R7") (pin "2") (pinfunction "2_2") (pintype "passive"))
      (node (ref "U7") (pin "28") (pinfunction "AN13/C3IN2-/U2CTS/FLT6/PMA10/RE13_28") (pintype "bidirectional"))
    )
    (net (code "58") (name "Net-(U7-PGEC3{slash}VREF+{slash}CVREF+{slash}OA1OUT{slash}AN3{slash}C1IN4-{slash}C4IN2-{slash}RPI33{slash}CTED1{slash}RB1)") (class "Default")
      (node (ref "ICSP") (pin "5") (pinfunction "5_5") (pintype "passive"))
      (node (ref "U7") (pin "16") (pinfunction "PGEC3/VREF+/CVREF+/OA1OUT/AN3/C1IN4-/C4IN2-/RPI33/CTED1/RB1_16") (pintype "bidirectional"))
    )
    (net (code "59") (name "Net-(U7-PGED3{slash}VREF-{slash}OA2IN-{slash}AN2{slash}C2IN1-{slash}SS1{slash}RPI32{slash}CTED2{slash}RB0)") (class "Default")
      (node (ref "ICSP") (pin "4") (pinfunction "4_4") (pintype "passive"))
      (node (ref "U7") (pin "15") (pinfunction "PGED3/VREF-/OA2IN-/AN2/C2IN1-/SS1/RPI32/CTED2/RB0_15") (pintype "bidirectional"))
    )
    (net (code "60") (name "Net-(U7-~{MCLR}*)") (class "Default")
      (node (ref "R14") (pin "2") (pinfunction "2_2") (pintype "passive"))
      (node (ref "U7") (pin "7") (pinfunction "~{MCLR}*_7") (pintype "bidirectional"))
    )
    (net (code "61") (name "Net-(U10-SCL)") (class "Default")
      (node (ref "R16") (pin "1") (pinfunction "1_1") (pintype "passive"))
      (node (ref "U10") (pin "1") (pinfunction "SCL_1") (pintype "bidirectional"))
      (node (ref "U7") (pin "32") (pinfunction "FLT32/SCL2/RP36/PMA8/RB4*_32") (pintype "bidirectional"))
    )
    (net (code "62") (name "Net-(U10-SDA)") (class "Default")
      (node (ref "R13") (pin "1") (pinfunction "1_1") (pintype "passive"))
      (node (ref "U10") (pin "3") (pinfunction "SDA_3") (pintype "bidirectional"))
      (node (ref "U7") (pin "31") (pinfunction "SDA2/RPI24/PMA9/RA8*_31") (pintype "bidirectional"))
    )
    (net (code "63") (name "unconnected-(CARD1-Pad1)") (class "Default")
      (node (ref "CARD1") (pin "1") (pinfunction "1_1") (pintype "passive"))
    )
    (net (code "64") (name "unconnected-(CARD1-Pad3)") (class "Default")
      (node (ref "CARD1") (pin "3") (pinfunction "3_3") (pintype "passive"))
    )
    (net (code "65") (name "unconnected-(CARD1-Pad4)") (class "Default")
      (node (ref "CARD1") (pin "4") (pinfunction "4_4") (pintype "passive"))
    )
    (net (code "66") (name "unconnected-(CARD1-Pad5)") (class "Default")
      (node (ref "CARD1") (pin "5") (pinfunction "5_5") (pintype "passive"))
    )
    (net (code "67") (name "unconnected-(CARD1-Pad6)") (class "Default")
      (node (ref "CARD1") (pin "6") (pinfunction "6_6") (pintype "passive"))
    )
    (net (code "68") (name "unconnected-(CARD1-Pad7)") (class "Default")
      (node (ref "CARD1") (pin "7") (pinfunction "7_7") (pintype "passive"))
    )
    (net (code "69") (name "unconnected-(CARD1-Pad8)") (class "Default")
      (node (ref "CARD1") (pin "8") (pinfunction "8_8") (pintype "passive"))
    )
    (net (code "70") (name "unconnected-(CARD1-Pad10)") (class "Default")
      (node (ref "CARD1") (pin "10") (pinfunction "10_10") (pintype "passive"))
    )
    (net (code "71") (name "unconnected-(CARD1-Pad12)") (class "Default")
      (node (ref "CARD1") (pin "12") (pinfunction "12_12") (pintype "passive"))
    )
    (net (code "72") (name "unconnected-(CARD1-Pad14)") (class "Default")
      (node (ref "CARD1") (pin "14") (pinfunction "14_14") (pintype "passive"))
    )
    (net (code "73") (name "unconnected-(CARD1-Pad16)") (class "Default")
      (node (ref "CARD1") (pin "16") (pinfunction "16_16") (pintype "passive"))
    )
    (net (code "74") (name "unconnected-(CARD1B-2-Pad18)") (class "Default")
      (node (ref "CARD1") (pin "18") (pinfunction "2_18") (pintype "passive"))
    )
    (net (code "75") (name "unconnected-(CARD1B-4-Pad20)") (class "Default")
      (node (ref "CARD1") (pin "20") (pinfunction "4_20") (pintype "passive"))
    )
    (net (code "76") (name "unconnected-(CARD1B-5-Pad21)") (class "Default")
      (node (ref "CARD1") (pin "21") (pinfunction "5_21") (pintype "passive"))
    )
    (net (code "77") (name "unconnected-(CARD1B-6-Pad22)") (class "Default")
      (node (ref "CARD1") (pin "22") (pinfunction "6_22") (pintype "passive"))
    )
    (net (code "78") (name "unconnected-(CARD1B-7-Pad23)") (class "Default")
      (node (ref "CARD1") (pin "23") (pinfunction "7_23") (pintype "passive"))
    )
    (net (code "79") (name "unconnected-(CARD1B-8-Pad24)") (class "Default")
      (node (ref "CARD1") (pin "24") (pinfunction "8_24") (pintype "passive"))
    )
    (net (code "80") (name "unconnected-(CARD1B-9-Pad25)") (class "Default")
      (node (ref "CARD1") (pin "25") (pinfunction "9_25") (pintype "passive"))
    )
    (net (code "81") (name "unconnected-(CARD1B-10-Pad26)") (class "Default")
      (node (ref "CARD1") (pin "26") (pinfunction "10_26") (pintype "passive"))
    )
    (net (code "82") (name "unconnected-(CARD1B-11-Pad27)") (class "Default")
      (node (ref "CARD1") (pin "27") (pinfunction "11_27") (pintype "passive"))
    )
    (net (code "83") (name "unconnected-(CARD1B-12-Pad28)") (class "Default")
      (node (ref "CARD1") (pin "28") (pinfunction "12_28") (pintype "passive"))
    )
    (net (code "84") (name "unconnected-(CARD1B-13-Pad29)") (class "Default")
      (node (ref "CARD1") (pin "29") (pinfunction "13_29") (pintype "passive"))
    )
    (net (code "85") (name "unconnected-(CARD1B-14-Pad30)") (class "Default")
      (node (ref "CARD1") (pin "30") (pinfunction "14_30") (pintype "passive"))
    )
    (net (code "86") (name "unconnected-(CARD1B-15-Pad31)") (class "Default")
      (node (ref "CARD1") (pin "31") (pinfunction "15_31") (pintype "passive"))
    )
    (net (code "87") (name "unconnected-(U1-ANT_ON-Pad30)") (class "Default")
      (node (ref "U1") (pin "30") (pinfunction "ANT_ON_30") (pintype "bidirectional"))
    )
    (net (code "88") (name "unconnected-(U1-EXTINT-Pad7)") (class "Default")
      (node (ref "U1") (pin "7") (pinfunction "EXTINT_7") (pintype "bidirectional"))
    )
    (net (code "89") (name "unconnected-(U1-RESET_N-Pad23)") (class "Default")
      (node (ref "U1") (pin "23") (pinfunction "RESET_N_23") (pintype "bidirectional"))
    )
    (net (code "90") (name "unconnected-(U1-TIMEPULSE-Pad29)") (class "Default")
      (node (ref "U1") (pin "29") (pinfunction "TIMEPULSE_29") (pintype "bidirectional"))
    )
    (net (code "91") (name "unconnected-(U4-CBUS0-Pad15)") (class "Default")
      (node (ref "U4") (pin "15") (pinfunction "CBUS0_15") (pintype "bidirectional"))
    )
    (net (code "92") (name "unconnected-(U5-DNC-Pad8)") (class "Default")
      (node (ref "U5") (pin "8") (pinfunction "DNC_8") (pintype "bidirectional"))
    )
    (net (code "93") (name "unconnected-(U5-GIO_0-Pad7)") (class "Default")
      (node (ref "U5") (pin "7") (pinfunction "GIO_0_7") (pintype "bidirectional"))
    )
    (net (code "94") (name "unconnected-(U5-GIO_1-Pad6)") (class "Default")
      (node (ref "U5") (pin "6") (pinfunction "GIO_1_6") (pintype "bidirectional"))
    )
    (net (code "95") (name "unconnected-(U5-GIO_2-Pad17)") (class "Default")
      (node (ref "U5") (pin "17") (pinfunction "GIO_2_17") (pintype "bidirectional"))
    )
    (net (code "96") (name "unconnected-(U5-GIO_3-Pad19)") (class "Default")
      (node (ref "U5") (pin "19") (pinfunction "GIO_3_19") (pintype "bidirectional"))
    )
    (net (code "97") (name "unconnected-(U5-GIO_4-Pad14)") (class "Default")
      (node (ref "U5") (pin "14") (pinfunction "GIO_4_14") (pintype "bidirectional"))
    )
    (net (code "98") (name "unconnected-(U5-GIO_5-Pad13)") (class "Default")
      (node (ref "U5") (pin "13") (pinfunction "GIO_5_13") (pintype "bidirectional"))
    )
    (net (code "99") (name "unconnected-(U5-GIO_6-Pad4)") (class "Default")
      (node (ref "U5") (pin "4") (pinfunction "GIO_6_4") (pintype "bidirectional"))
    )
    (net (code "100") (name "unconnected-(U5-GIO_7-Pad20)") (class "Default")
      (node (ref "U5") (pin "20") (pinfunction "GIO_7_20") (pintype "bidirectional"))
    )
    (net (code "101") (name "unconnected-(U5-GIO_8-Pad18)") (class "Default")
      (node (ref "U5") (pin "18") (pinfunction "GIO_8_18") (pintype "bidirectional"))
    )
    (net (code "102") (name "unconnected-(U5-~{9600}-Pad9)") (class "Default")
      (node (ref "U5") (pin "9") (pinfunction "~{9600}_9") (pintype "bidirectional"))
    )
    (net (code "103") (name "unconnected-(U5-~{CTS}-Pad12)") (class "Default")
      (node (ref "U5") (pin "12") (pinfunction "~{CTS}_12") (pintype "bidirectional"))
    )
    (net (code "104") (name "unconnected-(U5-~{RSET}-Pad5)") (class "Default")
      (node (ref "U5") (pin "5") (pinfunction "~{RSET}_5") (pintype "bidirectional"))
    )
    (net (code "105") (name "unconnected-(U5-~{RTS}-Pad16)") (class "Default")
      (node (ref "U5") (pin "16") (pinfunction "~{RTS}_16") (pintype "bidirectional"))
    )
    (net (code "106") (name "unconnected-(U7-*RP69{slash}PMRD{slash}RD5-Pad53)") (class "Default")
      (node (ref "U7") (pin "53") (pinfunction "*RP69/PMRD/RD5_53") (pintype "bidirectional"))
    )
    (net (code "107") (name "unconnected-(U7-*RPI44{slash}PWM2H{slash}PMD2{slash}RB12-Pad62)") (class "Default")
      (node (ref "U7") (pin "62") (pinfunction "*RPI44/PWM2H/PMD2/RB12_62") (pintype "bidirectional"))
    )
    (net (code "108") (name "unconnected-(U7-*RPI45{slash}PWM2L{slash}CTPLS{slash}PMD3{slash}RB13-Pad63)") (class "Default")
      (node (ref "U7") (pin "63") (pinfunction "*RPI45/PWM2L/CTPLS/PMD3/RB13_63") (pintype "bidirectional"))
    )
    (net (code "109") (name "unconnected-(U7-*RPI96{slash}RF0-Pad58)") (class "Default")
      (node (ref "U7") (pin "58") (pinfunction "*RPI96/RF0_58") (pintype "bidirectional"))
    )
    (net (code "110") (name "unconnected-(U7-*TDO{slash}PWM4H{slash}PMD4{slash}RA10-Pad64)") (class "Default")
      (node (ref "U7") (pin "64") (pinfunction "*TDO/PWM4H/PMD4/RA10_64") (pintype "bidirectional"))
    )
    (net (code "111") (name "unconnected-(U7-AN9{slash}RPI27{slash}RA11-Pad12)") (class "Default")
      (node (ref "U7") (pin "12") (pinfunction "AN9/RPI27/RA11_12") (pintype "bidirectional"))
    )
    (net (code "112") (name "unconnected-(U7-AN10{slash}RPI28{slash}RA12-Pad11)") (class "Default")
      (node (ref "U7") (pin "11") (pinfunction "AN10/RPI28/RA12_11") (pintype "bidirectional"))
    )
    (net (code "113") (name "unconnected-(U7-AN12{slash}C2IN2-{slash}C5IN2-{slash}U2RTS{slash}BCLK2{slash}FLT5{slash}PMA11{slash}RE12-Pad27)") (class "Default")
      (node (ref "U7") (pin "27") (pinfunction "AN12/C2IN2-/C5IN2-/U2RTS/BCLK2/FLT5/PMA11/RE12_27") (pintype "bidirectional"))
    )
    (net (code "114") (name "unconnected-(U7-AN14{slash}RPI94{slash}FLT7{slash}PMA1{slash}RE14-Pad29)") (class "Default")
      (node (ref "U7") (pin "29") (pinfunction "AN14/RPI94/FLT7/PMA1/RE14_29") (pintype "bidirectional"))
    )
    (net (code "115") (name "unconnected-(U7-AN15{slash}RPI95{slash}FLT8{slash}PMA0{slash}RE15-Pad30)") (class "Default")
      (node (ref "U7") (pin "30") (pinfunction "AN15/RPI95/FLT8/PMA0/RE15_30") (pintype "bidirectional"))
    )
    (net (code "116") (name "unconnected-(U7-AN16{slash}RPI121{slash}PMA2{slash}RG9-Pad8)") (class "Default")
      (node (ref "U7") (pin "8") (pinfunction "AN16/RPI121/PMA2/RG9_8") (pintype "bidirectional"))
    )
    (net (code "117") (name "unconnected-(U7-AN17{slash}ASDA1{slash}RP120{slash}PMA3{slash}RG8-Pad6)") (class "Default")
      (node (ref "U7") (pin "6") (pinfunction "AN17/ASDA1/RP120/PMA3/RG8_6") (pintype "bidirectional"))
    )
    (net (code "118") (name "unconnected-(U7-AN18{slash}ASCL1{slash}RPI119{slash}PMA4{slash}RG7-Pad5)") (class "Default")
      (node (ref "U7") (pin "5") (pinfunction "AN18/ASCL1/RPI119/PMA4/RG7_5") (pintype "bidirectional"))
    )
    (net (code "119") (name "unconnected-(U7-AN19{slash}RP118{slash}PMA5{slash}RG6-Pad4)") (class "Default")
      (node (ref "U7") (pin "4") (pinfunction "AN19/RP118/PMA5/RG6_4") (pintype "bidirectional"))
    )
    (net (code "120") (name "unconnected-(U7-AN28{slash}SDI1{slash}RPI25{slash}RA9-Pad34)") (class "Default")
      (node (ref "U7") (pin "34") (pinfunction "AN28/SDI1/RPI25/RA9_34") (pintype "bidirectional"))
    )
    (net (code "121") (name "unconnected-(U7-AN29{slash}SCK1{slash}RPI51{slash}RC3-Pad35)") (class "Default")
      (node (ref "U7") (pin "35") (pinfunction "AN29/SCK1/RPI51/RC3_35") (pintype "bidirectional"))
    )
    (net (code "122") (name "unconnected-(U7-AN30{slash}SDA1{slash}RPI52{slash}RC4-Pad36)") (class "Default")
      (node (ref "U7") (pin "36") (pinfunction "AN30/SDA1/RPI52/RC4_36") (pintype "bidirectional"))
    )
    (net (code "123") (name "unconnected-(U7-AN31{slash}SCL1{slash}RPI53{slash}RC5-Pad37)") (class "Default")
      (node (ref "U7") (pin "37") (pinfunction "AN31/SCL1/RPI53/RC5_37") (pintype "bidirectional"))
    )
    (net (code "124") (name "unconnected-(U7-AN48{slash}CVREF2O{slash}RPI58{slash}PMCS1{slash}RC10-Pad45)") (class "Default")
      (node (ref "U7") (pin "45") (pinfunction "AN48/CVREF2O/RPI58/PMCS1/RC10_45") (pintype "bidirectional"))
    )
    (net (code "125") (name "unconnected-(U7-OA2IN+{slash}AN1{slash}C2IN1+{slash}RPI17{slash}RA1-Pad14)") (class "Default")
      (node (ref "U7") (pin "14") (pinfunction "OA2IN+/AN1/C2IN1+/RPI17/RA1_14") (pintype "bidirectional"))
    )
    (net (code "126") (name "unconnected-(U7-OA2OUT{slash}AN0{slash}C2IN4-{slash}C4IN3-{slash}RPI16{slash}RA0-Pad13)") (class "Default")
      (node (ref "U7") (pin "13") (pinfunction "OA2OUT/AN0/C2IN4-/C4IN3-/RPI16/RA0_13") (pintype "bidirectional"))
    )
    (net (code "127") (name "unconnected-(U7-OA5IN+{slash}AN24{slash}C5IN3-{slash}C5IN1+{slash}SDO1{slash}RP20{slash}T1CK{slash}RA4-Pad33)") (class "Default")
      (node (ref "U7") (pin "33") (pinfunction "OA5IN+/AN24/C5IN3-/C5IN1+/SDO1/RP20/T1CK/RA4_33") (pintype "bidirectional"))
    )
    (net (code "128") (name "unconnected-(U7-OA5OUT{slash}AN25{slash}C5IN4-{slash}RP39{slash}INT0{slash}RB7-Pad46)") (class "Default")
      (node (ref "U7") (pin "46") (pinfunction "OA5OUT/AN25/C5IN4-/RP39/INT0/RB7_46") (pintype "bidirectional"))
    )
    (net (code "129") (name "unconnected-(U7-PGEC1{slash}OA1IN+{slash}AN4{slash}C1IN3-{slash}C1IN1+{slash}C2IN3-{slash}RPI34{slash}RB2-Pad17)") (class "Default")
      (node (ref "U7") (pin "17") (pinfunction "PGEC1/OA1IN+/AN4/C1IN3-/C1IN1+/C2IN3-/RPI34/RB2_17") (pintype "bidirectional"))
    )
    (net (code "130") (name "unconnected-(U7-PGEC2{slash}ASCL2{slash}RP38{slash}PMCS2{slash}RB6*-Pad44)") (class "Default")
      (node (ref "U7") (pin "44") (pinfunction "PGEC2/ASCL2/RP38/PMCS2/RB6*_44") (pintype "bidirectional"))
    )
    (net (code "131") (name "unconnected-(U7-PGED1{slash}OA1IN-{slash}AN5{slash}C1IN1-{slash}(CTMUC){slash}RP35{slash}RTCC{slash}RB3-Pad18)") (class "Default")
      (node (ref "U7") (pin "18") (pinfunction "PGED1/OA1IN-/AN5/C1IN1-/(CTMUC)/RP35/RTCC/RB3_18") (pintype "bidirectional"))
    )
    (net (code "132") (name "unconnected-(U7-PGED2{slash}ASDA2{slash}RP37{slash}RB5*-Pad43)") (class "Default")
      (node (ref "U7") (pin "43") (pinfunction "PGED2/ASDA2/RP37/RB5*_43") (pintype "bidirectional"))
    )
    (net (code "133") (name "unconnected-(U7-RPI46{slash}PWM1H{slash}T3CK{slash}T7CK{slash}PMD6{slash}RB14*-Pad2)") (class "Default")
      (node (ref "U7") (pin "2") (pinfunction "RPI46/PWM1H/T3CK/T7CK/PMD6/RB14*_2") (pintype "bidirectional"))
    )
    (net (code "134") (name "unconnected-(U7-RPI47{slash}PWM1L{slash}T5CK{slash}T6CK{slash}PMD7{slash}RB15*-Pad3)") (class "Default")
      (node (ref "U7") (pin "3") (pinfunction "RPI47/PWM1L/T5CK/T6CK/PMD7/RB15*_3") (pintype "bidirectional"))
    )
    (net (code "135") (name "unconnected-(U7-RPI72{slash}RD8*-Pad42)") (class "Default")
      (node (ref "U7") (pin "42") (pinfunction "RPI72/RD8*_42") (pintype "bidirectional"))
    )
    (net (code "136") (name "unconnected-(U7-SOSCI{slash}RPI61{slash}RC13-Pad47)") (class "Default")
      (node (ref "U7") (pin "47") (pinfunction "SOSCI/RPI61/RC13_47") (pintype "bidirectional"))
    )
    (net (code "137") (name "unconnected-(U7-TCK{slash}AN26{slash}CVREF1O{slash}SOSCO{slash}RP40{slash}T4CK{slash}RB8-Pad48)") (class "Default")
      (node (ref "U7") (pin "48") (pinfunction "TCK/AN26/CVREF1O/SOSCO/RP40/T4CK/RB8_48") (pintype "bidirectional"))
    )
    (net (code "138") (name "unconnected-(U7-TDI{slash}PWM4L{slash}PMD5{slash}RA7*-Pad1)") (class "Default")
      (node (ref "U7") (pin "1") (pinfunction "TDI/PWM4L/PMD5/RA7*_1") (pintype "bidirectional"))
    )
  )
)
